# untitled.net
KiCad netlist of a schematic drawn in EAGLE
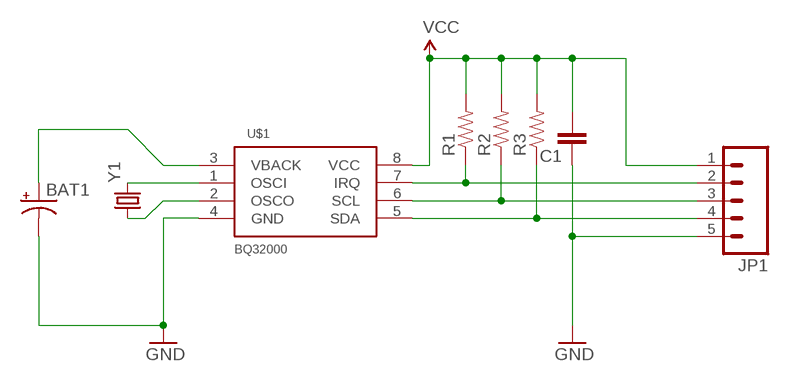
[diagram p0: schematic, sheet 1]

(export (version "E")
  (design (tool "Eeschema 10.0.6"))
  (components
    (comp (ref "BAT1")
      (value "CAP_POLPTH3")
      (footprint "eagle-import:CPOL-RADIAL-1000UF-63V")
      (libsource (lib "eagle-import") (part "CAP_POLPTH3"))
    )
    (comp (ref "C1")
      (value "CAP0805")
      (footprint "eagle-import:0805")
      (libsource (lib "eagle-import") (part "CAP0805"))
    )
    (comp (ref "JP1")
      (value "M05LOCK")
      (footprint "eagle-import:1X05_LOCK")
      (libsource (lib "eagle-import") (part "M05LOCK"))
    )
    (comp (ref "R1")
      (value "RESISTOR0805-RES")
      (footprint "eagle-import:0805")
      (libsource (lib "eagle-import") (part "RESISTOR0805-RES"))
    )
    (comp (ref "R2")
      (value "RESISTOR0805-RES")
      (footprint "eagle-import:0805")
      (libsource (lib "eagle-import") (part "RESISTOR0805-RES"))
    )
    (comp (ref "R3")
      (value "RESISTOR0805-RES")
      (footprint "eagle-import:0805")
      (libsource (lib "eagle-import") (part "RESISTOR0805-RES"))
    )
    (comp (ref "U$1")
      (value "BQ32000")
      (footprint "eagle-import:SO08")
      (libsource (lib "eagle-import") (part "BQ32000"))
    )
    (comp (ref "Y1")
      (value "CRYSTAL32-SMD")
      (footprint "eagle-import:CRYSTAL-32KHZ-SMD")
      (libsource (lib "eagle-import") (part "CRYSTAL32-SMD"))
    )
  )
  (nets
    (net (code "1") (name "GND") (class "Default")
      (node (ref "BAT1") (pin "2") (pinfunction "-_2") (pintype "passive"))
      (node (ref "C1") (pin "1") (pinfunction "1_1") (pintype "passive"))
      (node (ref "JP1") (pin "5") (pinfunction "5_5") (pintype "passive"))
      (node (ref "U$1") (pin "4") (pinfunction "GND_4") (pintype "bidirectional"))
    )
    (net (code "2") (name "Net-(BAT1-+)") (class "Default")
      (node (ref "BAT1") (pin "1") (pinfunction "+_1") (pintype "passive"))
      (node (ref "U$1") (pin "3") (pinfunction "VBACK_3") (pintype "bidirectional"))
    )
    (net (code "3") (name "Net-(U$1-IRQ)") (class "Default")
      (node (ref "JP1") (pin "2") (pinfunction "2_2") (pintype "passive"))
      (node (ref "R1") (pin "1") (pinfunction "1_1") (pintype "passive"))
      (node (ref "U$1") (pin "7") (pinfunction "IRQ_7") (pintype "output"))
    )
    (net (code "4") (name "Net-(U$1-OSCI)") (class "Default")
      (node (ref "U$1") (pin "1") (pinfunction "OSCI_1") (pintype "bidirectional"))
      (node (ref "Y1") (pin "X2") (pinfunction "2_X2") (pintype "passive"))
    )
    (net (code "5") (name "Net-(U$1-OSCO)") (class "Default")
      (node (ref "U$1") (pin "2") (pinfunction "OSCO_2") (pintype "bidirectional"))
      (node (ref "Y1") (pin "X1") (pinfunction "1_X1") (pintype "passive"))
    )
    (net (code "6") (name "Net-(U$1-SCL)") (class "Default")
      (node (ref "JP1") (pin "3") (pinfunction "3_3") (pintype "passive"))
      (node (ref "R2") (pin "1") (pinfunction "1_1") (pintype "passive"))
      (node (ref "U$1") (pin "6") (pinfunction "SCL_6") (pintype "input"))
    )
    (net (code "7") (name "Net-(U$1-SDA)") (class "Default")
      (node (ref "JP1") (pin "4") (pinfunction "4_4") (pintype "passive"))
      (node (ref "R3") (pin "1") (pinfunction "1_1") (pintype "passive"))
      (node (ref "U$1") (pin "5") (pinfunction "SDA_5") (pintype "bidirectional"))
    )
    (net (code "8") (name "VCC") (class "Default")
      (node (ref "C1") (pin "2") (pinfunction "2_2") (pintype "passive"))
      (node (ref "JP1") (pin "1") (pinfunction "1_1") (pintype "passive"))
      (node (ref "R1") (pin "2") (pinfunction "2_2") (pintype "passive"))
      (node (ref "R2") (pin "2") (pinfunction "2_2") (pintype "passive"))
      (node (ref "R3") (pin "2") (pinfunction "2_2") (pintype "passive"))
      (node (ref "U$1") (pin "8") (pinfunction "VCC_8") (pintype "power_in"))
    )
  )
)
